# TX_fsi6.net
KiCad netlist of a schematic drawn in Altium Designer
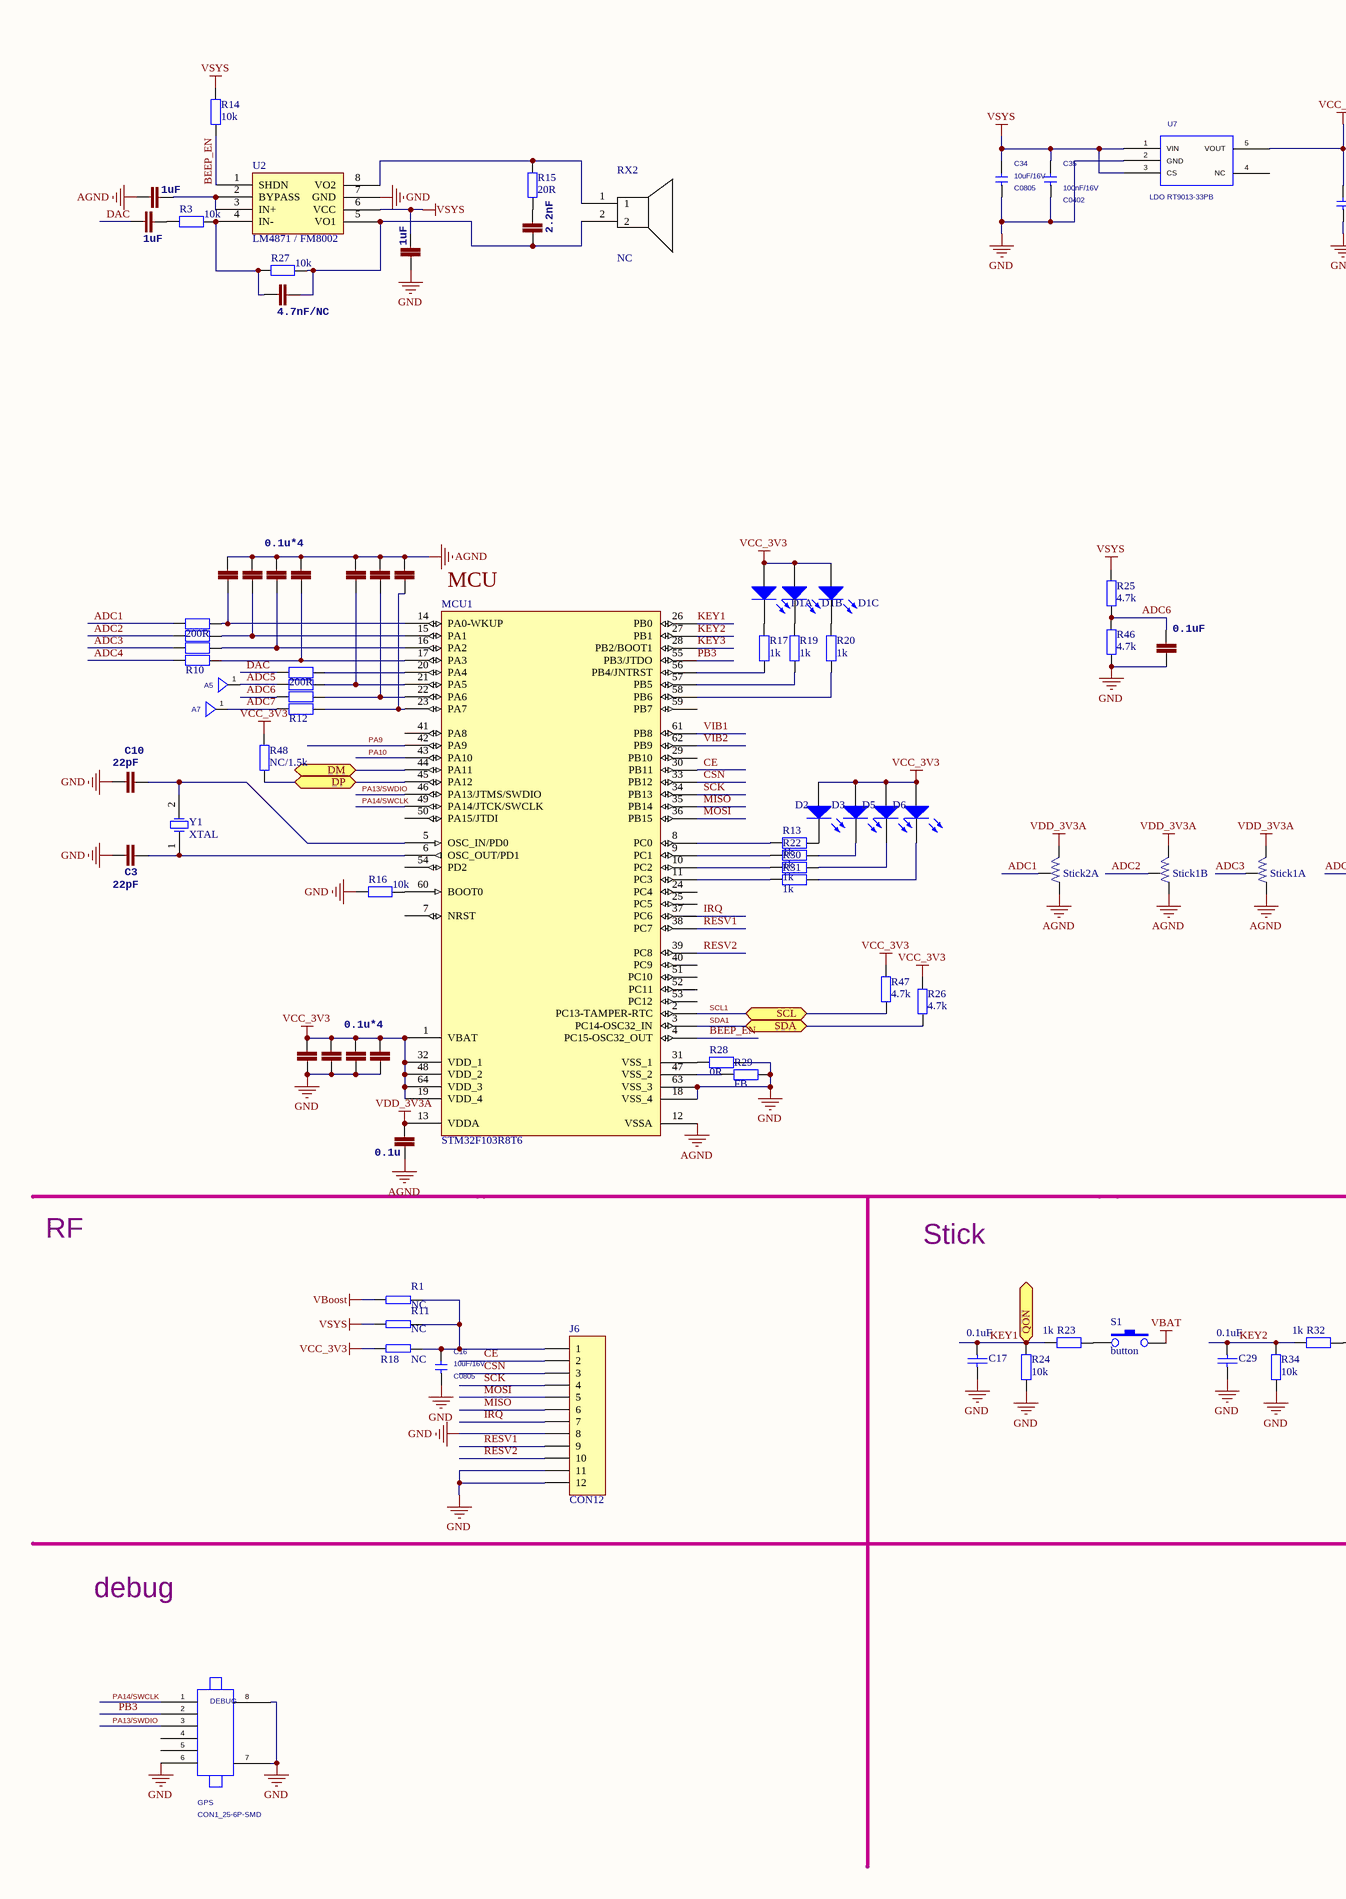
[diagram p0: TX_fsi6.SchDoc, left]
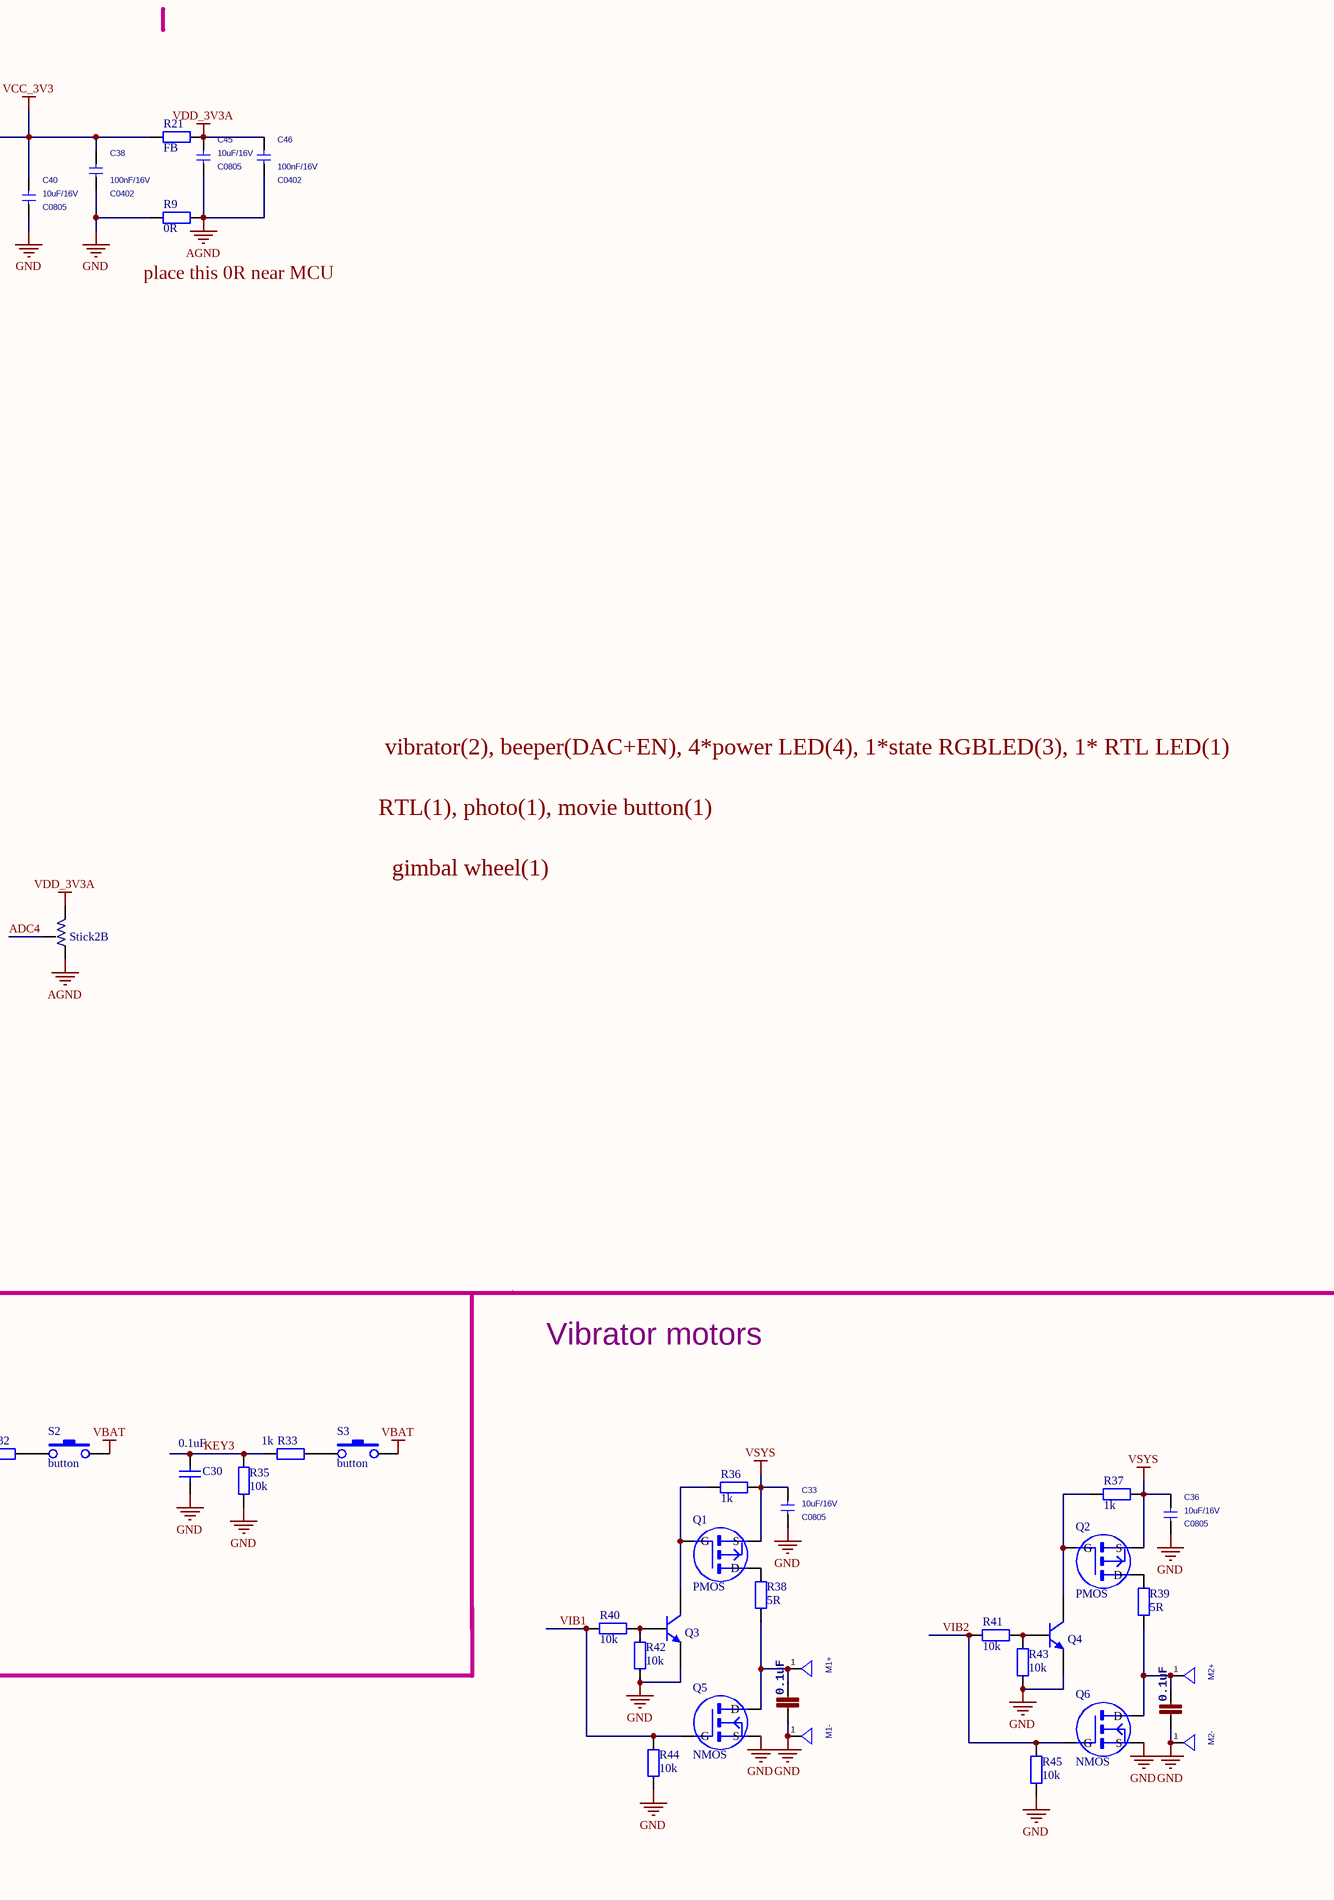
[diagram p1: TX_fsi6.SchDoc, right]

(export (version "E")
  (design (tool "Eeschema 10.0.6"))
  (components
    (comp (ref "A5") (value "~") (footprint "TestPad - 1mm") (libsource (lib "*") (part "TP_5")))
    (comp (ref "A7") (value "~") (footprint "TestPad - 1mm") (libsource (lib "*") (part "TP_5")))
    (comp (ref "C3")
      (value "22pF")
      (footprint "0402")
      (description "<b>Capacitor</b>\nStandard 0603 ceramic capacitor, and 0.1\" leaded capacitor.")
      (fields (field (name "PARTNO") "CC0402ZRY5V7BB104"))
      (libsource (lib "*") (part "CAP0402-CAP"))
    )
    (comp (ref "C7")
      (value "1n")
      (footprint "0402")
      (description "<b>Capacitor</b>\nStandard 0603 ceramic capacitor, and 0.1\" leaded capacitor.")
      (fields (field (name "PARTNO") "CC0402ZRY5V7BB104"))
      (libsource (lib "pixhawk2") (part "CAP0402-CAP"))
    )
    (comp (ref "C8")
      (value "1n")
      (footprint "0402")
      (description "<b>Capacitor</b>\nStandard 0603 ceramic capacitor, and 0.1\" leaded capacitor.")
      (fields (field (name "PARTNO") "CC0402ZRY5V7BB104"))
      (libsource (lib "pixhawk2") (part "CAP0402-CAP"))
    )
    (comp (ref "C9")
      (value "1n")
      (footprint "0402")
      (description "<b>Capacitor</b>\nStandard 0603 ceramic capacitor, and 0.1\" leaded capacitor.")
      (fields (field (name "PARTNO") "CC0402ZRY5V7BB104"))
      (libsource (lib "pixhawk2") (part "CAP0402-CAP"))
    )
    (comp (ref "C10")
      (value "22pF")
      (footprint "0402")
      (description "<b>Capacitor</b>\nStandard 0603 ceramic capacitor, and 0.1\" leaded capacitor.")
      (fields (field (name "PARTNO") "CC0402ZRY5V7BB104"))
      (libsource (lib "") (part "CAP0402-CAP_2"))
    )
    (comp (ref "C11")
      (value "0.1u*4")
      (footprint "0402")
      (description "<b>Capacitor</b>\nStandard 0603 ceramic capacitor, and 0.1\" leaded capacitor.")
      (fields (field (name "PARTNO") "CC0402ZRY5V7BB104"))
      (libsource (lib "pixhawk2") (part "CAP0402-CAP"))
    )
    (comp (ref "C12")
      (value "0.1u")
      (footprint "0402")
      (description "<b>Capacitor</b>\nStandard 0603 ceramic capacitor, and 0.1\" leaded capacitor.")
      (fields (field (name "PARTNO") "CC0402ZRY5V7BB104"))
      (libsource (lib "pixhawk2") (part "CAP0402-CAP"))
    )
    (comp (ref "C16")
      (value "10uF/16V")
      (footprint "0805")
      (fields (field (name "PCB DECAL") "C0805") (field (name "Comment") "C"))
      (libsource (lib "*") (part "C"))
    )
    (comp (ref "C17")
      (value "0.1uF")
      (footprint "0402")
      (description "Capacitor")
      (fields (field (name "PUBLISHER") "Altium Limited"))
      (libsource (lib "RTC6705") (part "Cap"))
    )
    (comp (ref "C18")
      (value "0.1u*4")
      (footprint "0402")
      (description "<b>Capacitor</b>\nStandard 0603 ceramic capacitor, and 0.1\" leaded capacitor.")
      (fields (field (name "PARTNO") "CC0402ZRY5V7BB104"))
      (libsource (lib "pixhawk2") (part "CAP0402-CAP"))
    )
    (comp (ref "C19")
      (value "1n")
      (footprint "0402")
      (description "<b>Capacitor</b>\nStandard 0603 ceramic capacitor, and 0.1\" leaded capacitor.")
      (fields (field (name "PARTNO") "CC0402ZRY5V7BB104"))
      (libsource (lib "pixhawk2") (part "CAP0402-CAP"))
    )
    (comp (ref "C20")
      (value "1n")
      (footprint "0402")
      (description "<b>Capacitor</b>\nStandard 0603 ceramic capacitor, and 0.1\" leaded capacitor.")
      (fields (field (name "PARTNO") "CC0402ZRY5V7BB104"))
      (libsource (lib "pixhawk2") (part "CAP0402-CAP"))
    )
    (comp (ref "C21")
      (value "1n")
      (footprint "0402")
      (description "<b>Capacitor</b>\nStandard 0603 ceramic capacitor, and 0.1\" leaded capacitor.")
      (fields (field (name "PARTNO") "CC0402ZRY5V7BB104"))
      (libsource (lib "pixhawk2") (part "CAP0402-CAP"))
    )
    (comp (ref "C22")
      (value "1n")
      (footprint "0402")
      (description "<b>Capacitor</b>\nStandard 0603 ceramic capacitor, and 0.1\" leaded capacitor.")
      (fields (field (name "PARTNO") "CC0402ZRY5V7BB104"))
      (libsource (lib "pixhawk2") (part "CAP0402-CAP"))
    )
    (comp (ref "C23")
      (value "1n")
      (footprint "0402")
      (description "<b>Capacitor</b>\nStandard 0603 ceramic capacitor, and 0.1\" leaded capacitor.")
      (fields (field (name "PARTNO") "CC0402ZRY5V7BB104"))
      (libsource (lib "pixhawk2") (part "CAP0402-CAP"))
    )
    (comp (ref "C24")
      (value "1n")
      (footprint "0402")
      (description "<b>Capacitor</b>\nStandard 0603 ceramic capacitor, and 0.1\" leaded capacitor.")
      (fields (field (name "PARTNO") "CC0402ZRY5V7BB104"))
      (libsource (lib "pixhawk2") (part "CAP0402-CAP"))
    )
    (comp (ref "C25")
      (value "1uF")
      (footprint "0603")
      (description "<b>Capacitor</b>\nStandard 0603 ceramic capacitor, and 0.1\" leaded capacitor.")
      (fields (field (name "PARTNO") "CC0402ZRY5V7BB104"))
      (libsource (lib "") (part "CAP0402-CAP_2"))
    )
    (comp (ref "C26")
      (value "1uF")
      (footprint "0603")
      (description "<b>Capacitor</b>\nStandard 0603 ceramic capacitor, and 0.1\" leaded capacitor.")
      (fields (field (name "PARTNO") "CC0402ZRY5V7BB104"))
      (libsource (lib "") (part "CAP0402-CAP_2"))
    )
    (comp (ref "C27")
      (value "4.7nF/NC")
      (footprint "0402")
      (description "<b>Capacitor</b>\nStandard 0603 ceramic capacitor, and 0.1\" leaded capacitor.")
      (fields (field (name "PARTNO") "CC0402ZRY5V7BB104"))
      (libsource (lib "") (part "CAP0402-CAP_2"))
    )
    (comp (ref "C28")
      (value "1uF")
      (footprint "0603")
      (description "<b>Capacitor</b>\nStandard 0603 ceramic capacitor, and 0.1\" leaded capacitor.")
      (fields (field (name "PARTNO") "CC0402ZRY5V7BB104"))
      (libsource (lib "") (part "CAP0402-CAP_1"))
    )
    (comp (ref "C29")
      (value "0.1uF")
      (footprint "0402")
      (description "Capacitor")
      (fields (field (name "PUBLISHER") "Altium Limited"))
      (libsource (lib "RTC6705") (part "Cap"))
    )
    (comp (ref "C30")
      (value "0.1uF")
      (footprint "0402")
      (description "Capacitor")
      (fields (field (name "PUBLISHER") "Altium Limited"))
      (libsource (lib "RTC6705") (part "Cap"))
    )
    (comp (ref "C32")
      (value "2.2nF")
      (footprint "0402")
      (description "<b>Capacitor</b>\nStandard 0603 ceramic capacitor, and 0.1\" leaded capacitor.")
      (fields (field (name "PARTNO") "CC0402ZRY5V7BB104"))
      (libsource (lib "") (part "CAP0402-CAP_1"))
    )
    (comp (ref "C33")
      (value "10uF/16V")
      (footprint "0805")
      (fields (field (name "PCB DECAL") "C0805") (field (name "Comment") "C"))
      (libsource (lib "*") (part "C"))
    )
    (comp (ref "C34")
      (value "10uF/16V")
      (footprint "0805")
      (fields (field (name "PCB DECAL") "C0805") (field (name "Comment") "C"))
      (libsource (lib "*") (part "C"))
    )
    (comp (ref "C35")
      (value "100nF/16V")
      (footprint "0603")
      (fields (field (name "PCB DECAL") "C0402") (field (name "Comment") "C"))
      (libsource (lib "*") (part "C"))
    )
    (comp (ref "C36")
      (value "10uF/16V")
      (footprint "0805")
      (fields (field (name "PCB DECAL") "C0805") (field (name "Comment") "C"))
      (libsource (lib "*") (part "C"))
    )
    (comp (ref "C37")
      (value "0.1uF")
      (footprint "0603")
      (description "<b>Capacitor</b>\nStandard 0603 ceramic capacitor, and 0.1\" leaded capacitor.")
      (fields (field (name "PARTNO") "CC0402ZRY5V7BB104"))
      (libsource (lib "") (part "CAP0402-CAP_1"))
    )
    (comp (ref "C38")
      (value "100nF/16V")
      (footprint "0603")
      (fields (field (name "PCB DECAL") "C0402") (field (name "Comment") "C"))
      (libsource (lib "*") (part "C"))
    )
    (comp (ref "C39")
      (value "0.1uF")
      (footprint "0603")
      (description "<b>Capacitor</b>\nStandard 0603 ceramic capacitor, and 0.1\" leaded capacitor.")
      (fields (field (name "PARTNO") "CC0402ZRY5V7BB104"))
      (libsource (lib "") (part "CAP0402-CAP_1"))
    )
    (comp (ref "C40")
      (value "10uF/16V")
      (footprint "0805")
      (fields (field (name "PCB DECAL") "C0805") (field (name "Comment") "C"))
      (libsource (lib "*") (part "C"))
    )
    (comp (ref "C41")
      (value "0.1uF")
      (footprint "0402")
      (description "<b>Capacitor</b>\nStandard 0603 ceramic capacitor, and 0.1\" leaded capacitor.")
      (fields (field (name "PARTNO") "CC0402ZRY5V7BB104"))
      (libsource (lib "pixhawk2") (part "CAP0402-CAP"))
    )
    (comp (ref "C45")
      (value "10uF/16V")
      (footprint "0805")
      (fields (field (name "PCB DECAL") "C0805") (field (name "Comment") "C"))
      (libsource (lib "*") (part "C"))
    )
    (comp (ref "C46")
      (value "100nF/16V")
      (footprint "0603")
      (fields (field (name "PCB DECAL") "C0402") (field (name "Comment") "C"))
      (libsource (lib "*") (part "C"))
    )
    (comp (ref "D1")
      (value "LEDx3")
      (footprint "LC-0603_Rx2")
      (description "Typical RED GaAs LED")
      (fields (field (name "PUBLISHER") "Altium Limited"))
      (libsource (lib "sch") (part "LEDx3"))
    )
    (comp (ref "D2")
      (value "LED0")
      (footprint "0603")
      (description "Typical INFRARED GaAs LED")
      (fields (field (name "PUBLISHER") "Altium Limited"))
      (libsource (lib "Miscellaneous Devices") (part "LED0"))
    )
    (comp (ref "D3")
      (value "LED0")
      (footprint "0603")
      (description "Typical INFRARED GaAs LED")
      (fields (field (name "PUBLISHER") "Altium Limited"))
      (libsource (lib "Miscellaneous Devices") (part "LED0"))
    )
    (comp (ref "D5")
      (value "LED0")
      (footprint "0603")
      (description "Typical INFRARED GaAs LED")
      (fields (field (name "PUBLISHER") "Altium Limited"))
      (libsource (lib "Miscellaneous Devices") (part "LED0"))
    )
    (comp (ref "D6")
      (value "LED0")
      (footprint "0603")
      (description "Typical INFRARED GaAs LED")
      (fields (field (name "PUBLISHER") "Altium Limited"))
      (libsource (lib "Miscellaneous Devices") (part "LED0"))
    )
    (comp (ref "DEBUG")
      (value "GPS")
      (footprint "CON1_25-6P-SMD")
      (fields (field (name "PCB DECAL") "CON1_25-6P-SMD") (field (name "Comment") "J12"))
      (libsource (lib "*") (part "J12"))
    )
    (comp (ref "J6")
      (value "CON12")
      (footprint "RF_AS01_SPIPX")
      (description "Connector")
      (libsource (lib "TITR-2011") (part "CON12"))
    )
    (comp (ref "M1+") (value "~") (footprint "TestPad") (libsource (lib "*") (part "TP_5")))
    (comp (ref "M1-") (value "~") (footprint "TestPad") (libsource (lib "*") (part "TP_5")))
    (comp (ref "M2+") (value "~") (footprint "TestPad") (libsource (lib "*") (part "TP_5")))
    (comp (ref "M2-") (value "~") (footprint "TestPad") (libsource (lib "*") (part "TP_5")))
    (comp (ref "MCU1")
      (value "STM32F103R8T6")
      (footprint "LQFP64_N")
      (description "STM32 ARM-based 32-bit MCU with 64 Kbytes Flash, 64-pin LQFP, Industrial Temperature")
      (fields (field (name "PUBLISHER") "*"))
      (libsource (lib "ST Microcontroller 32-Bit STM32 SCH") (part "STM32F103R8T6"))
    )
    (comp (ref "Q1") (value "PMOS") (footprint "SOT-23B_L") (libsource (lib "sch") (part "PMOS")))
    (comp (ref "Q2") (value "PMOS") (footprint "SOT-23B_L") (libsource (lib "sch") (part "PMOS")))
    (comp (ref "Q3")
      (value "NPN")
      (footprint "SOT-23B_L")
      (description "NPN Bipolar Transistor")
      (fields (field (name "PUBLISHER") "Altium Limited"))
      (libsource (lib "sch") (part "NPN"))
    )
    (comp (ref "Q4")
      (value "NPN")
      (footprint "SOT-23B_L")
      (description "NPN Bipolar Transistor")
      (fields (field (name "PUBLISHER") "Altium Limited"))
      (libsource (lib "sch") (part "NPN"))
    )
    (comp (ref "Q5") (value "NMOS") (footprint "SOT-23B_L") (libsource (lib "sch") (part "NMOS")))
    (comp (ref "Q6") (value "NMOS") (footprint "SOT-23B_L") (libsource (lib "sch") (part "NMOS")))
    (comp (ref "R1") (value "NC") (footprint "0603") (libsource (lib "Robomasters") (part "Res")))
    (comp (ref "R3")
      (value "10k")
      (footprint "0402")
      (description "Resistor")
      (fields (field (name "PUBLISHER") "Altium Limited"))
      (libsource (lib "") (part "Res2_2"))
    )
    (comp (ref "R9")
      (value "0R")
      (footprint "0402")
      (description "Resistor")
      (fields (field (name "PUBLISHER") "Altium Limited"))
      (libsource (lib "RTC6705") (part "Res2"))
    )
    (comp (ref "R10")
      (value "200R")
      (footprint "0402X4")
      (description "Resistor")
      (fields (field (name "PUBLISHER") "Altium Limited"))
      (libsource (lib "sch") (part "Res*4"))
    )
    (comp (ref "R11") (value "NC") (footprint "0603") (libsource (lib "Robomasters") (part "Res")))
    (comp (ref "R12")
      (value "200R")
      (footprint "0402X4")
      (description "Resistor")
      (fields (field (name "PUBLISHER") "Altium Limited"))
      (libsource (lib "sch") (part "Res*4"))
    )
    (comp (ref "R13")
      (value "1k")
      (footprint "0402")
      (description "Resistor")
      (fields (field (name "PUBLISHER") "Altium Limited"))
      (libsource (lib "") (part "Res2_1"))
    )
    (comp (ref "R14")
      (value "10k")
      (footprint "0402")
      (description "Resistor")
      (fields (field (name "PUBLISHER") "Altium Limited"))
      (libsource (lib "Miscellaneous Devices") (part "Res2"))
    )
    (comp (ref "R15")
      (value "20R")
      (footprint "0402")
      (description "Resistor")
      (fields (field (name "PUBLISHER") "Altium Limited"))
      (libsource (lib "Miscellaneous Devices") (part "Res2"))
    )
    (comp (ref "R16")
      (value "10k")
      (footprint "0402")
      (description "Resistor")
      (fields (field (name "PUBLISHER") "Altium Limited"))
      (libsource (lib "") (part "Res2_2"))
    )
    (comp (ref "R17")
      (value "1k")
      (footprint "0402")
      (description "Resistor")
      (fields (field (name "PUBLISHER") "Altium Limited"))
      (libsource (lib "Miscellaneous Devices") (part "Res2"))
    )
    (comp (ref "R18") (value "NC") (footprint "0603") (libsource (lib "Robomasters") (part "Res")))
    (comp (ref "R19")
      (value "1k")
      (footprint "0402")
      (description "Resistor")
      (fields (field (name "PUBLISHER") "Altium Limited"))
      (libsource (lib "Miscellaneous Devices") (part "Res2"))
    )
    (comp (ref "R20")
      (value "1k")
      (footprint "0402")
      (description "Resistor")
      (fields (field (name "PUBLISHER") "Altium Limited"))
      (libsource (lib "Miscellaneous Devices") (part "Res2"))
    )
    (comp (ref "R21")
      (value "FB")
      (footprint "0402")
      (description "Resistor")
      (fields (field (name "PUBLISHER") "Altium Limited"))
      (libsource (lib "RTC6705") (part "Res2"))
    )
    (comp (ref "R22")
      (value "1k")
      (footprint "0402")
      (description "Resistor")
      (fields (field (name "PUBLISHER") "Altium Limited"))
      (libsource (lib "") (part "Res2_1"))
    )
    (comp (ref "R23")
      (value "1k")
      (footprint "0402")
      (description "Resistor")
      (fields (field (name "PUBLISHER") "Altium Limited"))
      (libsource (lib "") (part "Res2_2"))
    )
    (comp (ref "R24")
      (value "10k")
      (footprint "0402")
      (description "Resistor")
      (fields (field (name "PUBLISHER") "Altium Limited"))
      (libsource (lib "") (part "Res2_1"))
    )
    (comp (ref "R25")
      (value "4.7k")
      (footprint "0402")
      (description "Resistor")
      (fields (field (name "PUBLISHER") "Altium Limited"))
      (libsource (lib "") (part "Res2_1"))
    )
    (comp (ref "R26")
      (value "4.7k")
      (footprint "0402")
      (description "Resistor")
      (fields (field (name "PUBLISHER") "Altium Limited"))
      (libsource (lib "") (part "Res2_1"))
    )
    (comp (ref "R27")
      (value "10k")
      (footprint "0402")
      (description "Resistor")
      (fields (field (name "PUBLISHER") "Altium Limited"))
      (libsource (lib "") (part "Res2_2"))
    )
    (comp (ref "R28")
      (value "0R")
      (footprint "0402")
      (description "Resistor")
      (fields (field (name "PUBLISHER") "Altium Limited"))
      (libsource (lib "RTC6705") (part "Res2"))
    )
    (comp (ref "R29")
      (value "FB")
      (footprint "0402")
      (description "Resistor")
      (fields (field (name "PUBLISHER") "Altium Limited"))
      (libsource (lib "RTC6705") (part "Res2"))
    )
    (comp (ref "R30")
      (value "1k")
      (footprint "0402")
      (description "Resistor")
      (fields (field (name "PUBLISHER") "Altium Limited"))
      (libsource (lib "") (part "Res2_1"))
    )
    (comp (ref "R31")
      (value "1k")
      (footprint "0402")
      (description "Resistor")
      (fields (field (name "PUBLISHER") "Altium Limited"))
      (libsource (lib "") (part "Res2_1"))
    )
    (comp (ref "R32")
      (value "1k")
      (footprint "0402")
      (description "Resistor")
      (fields (field (name "PUBLISHER") "Altium Limited"))
      (libsource (lib "") (part "Res2_2"))
    )
    (comp (ref "R33")
      (value "1k")
      (footprint "0402")
      (description "Resistor")
      (fields (field (name "PUBLISHER") "Altium Limited"))
      (libsource (lib "") (part "Res2_2"))
    )
    (comp (ref "R34")
      (value "10k")
      (footprint "0402")
      (description "Resistor")
      (fields (field (name "PUBLISHER") "Altium Limited"))
      (libsource (lib "") (part "Res2_1"))
    )
    (comp (ref "R35")
      (value "10k")
      (footprint "0402")
      (description "Resistor")
      (fields (field (name "PUBLISHER") "Altium Limited"))
      (libsource (lib "") (part "Res2_1"))
    )
    (comp (ref "R36")
      (value "1k")
      (footprint "0402")
      (description "Resistor")
      (fields (field (name "PUBLISHER") "Altium Limited"))
      (libsource (lib "RTC6705") (part "Res2"))
    )
    (comp (ref "R37")
      (value "1k")
      (footprint "0402")
      (description "Resistor")
      (fields (field (name "PUBLISHER") "Altium Limited"))
      (libsource (lib "RTC6705") (part "Res2"))
    )
    (comp (ref "R38")
      (value "5R")
      (footprint "0603")
      (description "Resistor")
      (fields (field (name "PUBLISHER") "Altium Limited"))
      (libsource (lib "") (part "Res2_1"))
    )
    (comp (ref "R39")
      (value "5R")
      (footprint "0603")
      (description "Resistor")
      (fields (field (name "PUBLISHER") "Altium Limited"))
      (libsource (lib "") (part "Res2_1"))
    )
    (comp (ref "R40")
      (value "10k")
      (footprint "0402")
      (description "Resistor")
      (fields (field (name "PUBLISHER") "Altium Limited"))
      (libsource (lib "RTC6705") (part "Res2"))
    )
    (comp (ref "R41")
      (value "10k")
      (footprint "0402")
      (description "Resistor")
      (fields (field (name "PUBLISHER") "Altium Limited"))
      (libsource (lib "RTC6705") (part "Res2"))
    )
    (comp (ref "R42")
      (value "10k")
      (footprint "0402")
      (description "Resistor")
      (fields (field (name "PUBLISHER") "Altium Limited"))
      (libsource (lib "") (part "Res2_1"))
    )
    (comp (ref "R43")
      (value "10k")
      (footprint "0402")
      (description "Resistor")
      (fields (field (name "PUBLISHER") "Altium Limited"))
      (libsource (lib "") (part "Res2_1"))
    )
    (comp (ref "R44")
      (value "10k")
      (footprint "0402")
      (description "Resistor")
      (fields (field (name "PUBLISHER") "Altium Limited"))
      (libsource (lib "") (part "Res2_1"))
    )
    (comp (ref "R45")
      (value "10k")
      (footprint "0402")
      (description "Resistor")
      (fields (field (name "PUBLISHER") "Altium Limited"))
      (libsource (lib "") (part "Res2_1"))
    )
    (comp (ref "R46")
      (value "4.7k")
      (footprint "0402")
      (description "Resistor")
      (fields (field (name "PUBLISHER") "Altium Limited"))
      (libsource (lib "") (part "Res2_1"))
    )
    (comp (ref "R47")
      (value "4.7k")
      (footprint "0402")
      (description "Resistor")
      (fields (field (name "PUBLISHER") "Altium Limited"))
      (libsource (lib "") (part "Res2_1"))
    )
    (comp (ref "R48")
      (value "NC/1.5k")
      (footprint "0402")
      (description "Resistor")
      (fields (field (name "PUBLISHER") "Altium Limited"))
      (libsource (lib "") (part "Res2_1"))
    )
    (comp (ref "RX2") (value "NC") (footprint "sonar-10mm") (libsource (lib "schlib") (part "sonar")))
    (comp (ref "S1")
      (value "button")
      (footprint "RubberButton-8mm")
      (libsource (lib "Euler") (part "button"))
    )
    (comp (ref "S2")
      (value "button")
      (footprint "RubberButton-8mm")
      (libsource (lib "Euler") (part "button"))
    )
    (comp (ref "S3")
      (value "button")
      (footprint "RubberButton-8mm")
      (libsource (lib "Euler") (part "button"))
    )
    (comp (ref "Stick1") (value "stick") (footprint "stick") (libsource (lib "sch") (part "stick")))
    (comp (ref "Stick2") (value "stick") (footprint "stick") (libsource (lib "sch") (part "stick")))
    (comp (ref "U2")
      (value "LM4871 / FM8002")
      (footprint "SOIC8_39MM")
      (libsource (lib "sch") (part "LM4871"))
    )
    (comp (ref "U7")
      (value "LDO RT9013-33PB")
      (footprint "SOT23-5")
      (fields (field (name "Comment") "RT9193-33_1_2"))
      (libsource (lib "*") (part "RT9193-33_1_2"))
    )
    (comp (ref "Y1")
      (value "XTAL")
      (footprint "OSCILLATOR-3.2X2.5 - 2P")
      (description "Crystal Oscillator")
      (fields (field (name "PUBLISHER") "Altium Limited"))
      (libsource (lib "Miscellaneous Devices") (part "XTAL"))
    )
  )
  (nets
    (net (code "1") (name "/ADC1") (class "Default")
      (node (ref "R10") (pin "1") (pinfunction "1_1") (pintype "passive"))
      (node (ref "Stick2") (pin "2") (pinfunction "2_2") (pintype "passive"))
    )
    (net (code "2") (name "/ADC2") (class "Default")
      (node (ref "R10") (pin "2") (pinfunction "2_2") (pintype "passive"))
      (node (ref "Stick1") (pin "5") (pinfunction "5_5") (pintype "passive"))
    )
    (net (code "3") (name "/ADC3") (class "Default")
      (node (ref "R10") (pin "3") (pinfunction "3_3") (pintype "passive"))
      (node (ref "Stick1") (pin "2") (pinfunction "2_2") (pintype "passive"))
    )
    (net (code "4") (name "/ADC4") (class "Default")
      (node (ref "R10") (pin "4") (pinfunction "4_4") (pintype "passive"))
      (node (ref "Stick2") (pin "5") (pinfunction "5_5") (pintype "passive"))
    )
    (net (code "5") (name "/ADC5") (class "Default")
      (node (ref "A5") (pin "1") (pinfunction "1_1") (pintype "passive"))
      (node (ref "R12") (pin "2") (pinfunction "2_2") (pintype "passive"))
    )
    (net (code "6") (name "/ADC6") (class "Default")
      (node (ref "C41") (pin "2") (pinfunction "2_2") (pintype "passive"))
      (node (ref "R12") (pin "3") (pinfunction "3_3") (pintype "passive"))
      (node (ref "R25") (pin "1") (pinfunction "1_1") (pintype "passive"))
      (node (ref "R46") (pin "2") (pinfunction "2_2") (pintype "passive"))
    )
    (net (code "7") (name "/ADC7") (class "Default")
      (node (ref "A7") (pin "1") (pinfunction "1_1") (pintype "passive"))
      (node (ref "R12") (pin "4") (pinfunction "4_4") (pintype "passive"))
    )
    (net (code "8") (name "/BEEP_EN") (class "Default")
      (node (ref "MCU1") (pin "4") (pinfunction "PC15-OSC32_OUT_4") (pintype "bidirectional"))
      (node (ref "R14") (pin "1") (pinfunction "1_1") (pintype "passive"))
      (node (ref "U2") (pin "1") (pinfunction "SHDN_1") (pintype "passive"))
    )
    (net (code "9") (name "/CE") (class "Default")
      (node (ref "J6") (pin "2") (pinfunction "2_2") (pintype "passive"))
      (node (ref "MCU1") (pin "30") (pinfunction "PB11_30") (pintype "bidirectional"))
    )
    (net (code "10") (name "/CSN") (class "Default")
      (node (ref "J6") (pin "3") (pinfunction "3_3") (pintype "passive"))
      (node (ref "MCU1") (pin "33") (pinfunction "PB12_33") (pintype "bidirectional"))
    )
    (net (code "11") (name "/DAC") (class "Default")
      (node (ref "C26") (pin "2") (pinfunction "2_2") (pintype "passive"))
      (node (ref "R12") (pin "1") (pinfunction "1_1") (pintype "passive"))
    )
    (net (code "12") (name "/DM") (class "Default")
      (node (ref "MCU1") (pin "44") (pinfunction "PA11_44") (pintype "bidirectional"))
    )
    (net (code "13") (name "/DP") (class "Default")
      (node (ref "MCU1") (pin "45") (pinfunction "PA12_45") (pintype "bidirectional"))
      (node (ref "R48") (pin "1") (pinfunction "1_1") (pintype "passive"))
    )
    (net (code "14") (name "/IRQ") (class "Default")
      (node (ref "J6") (pin "7") (pinfunction "7_7") (pintype "passive"))
      (node (ref "MCU1") (pin "37") (pinfunction "PC6_37") (pintype "bidirectional"))
    )
    (net (code "15") (name "/KEY1") (class "Default")
      (node (ref "C17") (pin "1") (pinfunction "1_1") (pintype "passive"))
      (node (ref "MCU1") (pin "26") (pinfunction "PB0_26") (pintype "bidirectional"))
      (node (ref "R23") (pin "1") (pinfunction "1_1") (pintype "passive"))
      (node (ref "R24") (pin "2") (pinfunction "2_2") (pintype "passive"))
    )
    (net (code "16") (name "/KEY2") (class "Default")
      (node (ref "C29") (pin "1") (pinfunction "1_1") (pintype "passive"))
      (node (ref "MCU1") (pin "27") (pinfunction "PB1_27") (pintype "bidirectional"))
      (node (ref "R32") (pin "1") (pinfunction "1_1") (pintype "passive"))
      (node (ref "R34") (pin "2") (pinfunction "2_2") (pintype "passive"))
    )
    (net (code "17") (name "/KEY3") (class "Default")
      (node (ref "C30") (pin "1") (pinfunction "1_1") (pintype "passive"))
      (node (ref "MCU1") (pin "28") (pinfunction "PB2/BOOT1_28") (pintype "bidirectional"))
      (node (ref "R33") (pin "1") (pinfunction "1_1") (pintype "passive"))
      (node (ref "R35") (pin "2") (pinfunction "2_2") (pintype "passive"))
    )
    (net (code "18") (name "/MISO") (class "Default")
      (node (ref "J6") (pin "6") (pinfunction "6_6") (pintype "passive"))
      (node (ref "MCU1") (pin "35") (pinfunction "PB14_35") (pintype "bidirectional"))
    )
    (net (code "19") (name "/MOSI") (class "Default")
      (node (ref "J6") (pin "5") (pinfunction "5_5") (pintype "passive"))
      (node (ref "MCU1") (pin "36") (pinfunction "PB15_36") (pintype "bidirectional"))
    )
    (net (code "20") (name "/PA9") (class "Default")
      (node (ref "MCU1") (pin "42") (pinfunction "PA9_42") (pintype "bidirectional"))
    )
    (net (code "21") (name "/PA10") (class "Default")
      (node (ref "MCU1") (pin "43") (pinfunction "PA10_43") (pintype "bidirectional"))
    )
    (net (code "22") (name "/PA13{slash}SWDIO") (class "Default")
      (node (ref "DEBUG") (pin "3") (pinfunction "3_3") (pintype "passive"))
      (node (ref "MCU1") (pin "46") (pinfunction "PA13/JTMS/SWDIO_46") (pintype "bidirectional"))
    )
    (net (code "23") (name "/PA14{slash}SWCLK") (class "Default")
      (node (ref "DEBUG") (pin "1") (pinfunction "1_1") (pintype "passive"))
      (node (ref "MCU1") (pin "49") (pinfunction "PA14/JTCK/SWCLK_49") (pintype "bidirectional"))
    )
    (net (code "24") (name "/PB3") (class "Default")
      (node (ref "DEBUG") (pin "2") (pinfunction "2_2") (pintype "passive"))
      (node (ref "MCU1") (pin "55") (pinfunction "PB3/JTDO_55") (pintype "bidirectional"))
    )
    (net (code "25") (name "/RESV1") (class "Default")
      (node (ref "J6") (pin "9") (pinfunction "9_9") (pintype "passive"))
      (node (ref "MCU1") (pin "38") (pinfunction "PC7_38") (pintype "bidirectional"))
    )
    (net (code "26") (name "/RESV2") (class "Default")
      (node (ref "J6") (pin "10") (pinfunction "10_10") (pintype "passive"))
      (node (ref "MCU1") (pin "39") (pinfunction "PC8_39") (pintype "bidirectional"))
    )
    (net (code "27") (name "/SCK") (class "Default")
      (node (ref "J6") (pin "4") (pinfunction "4_4") (pintype "passive"))
      (node (ref "MCU1") (pin "34") (pinfunction "PB13_34") (pintype "bidirectional"))
    )
    (net (code "28") (name "/SCL1") (class "Default")
      (node (ref "MCU1") (pin "2") (pinfunction "PC13-TAMPER-RTC_2") (pintype "bidirectional"))
      (node (ref "R47") (pin "1") (pinfunction "1_1") (pintype "passive"))
    )
    (net (code "29") (name "/SDA1") (class "Default")
      (node (ref "MCU1") (pin "3") (pinfunction "PC14-OSC32_IN_3") (pintype "bidirectional"))
      (node (ref "R26") (pin "1") (pinfunction "1_1") (pintype "passive"))
    )
    (net (code "30") (name "/VIB1") (class "Default")
      (node (ref "MCU1") (pin "61") (pinfunction "PB8_61") (pintype "bidirectional"))
      (node (ref "Q5") (pin "G") (pinfunction "G_G") (pintype "passive"))
      (node (ref "R40") (pin "2") (pinfunction "2_2") (pintype "passive"))
      (node (ref "R44") (pin "2") (pinfunction "2_2") (pintype "passive"))
    )
    (net (code "31") (name "/VIB2") (class "Default")
      (node (ref "MCU1") (pin "62") (pinfunction "PB9_62") (pintype "bidirectional"))
      (node (ref "Q6") (pin "G") (pinfunction "G_G") (pintype "passive"))
      (node (ref "R41") (pin "2") (pinfunction "2_2") (pintype "passive"))
      (node (ref "R45") (pin "2") (pinfunction "2_2") (pintype "passive"))
    )
    (net (code "32") (name "AGND") (class "Default")
      (node (ref "C12") (pin "1") (pinfunction "1_1") (pintype "passive"))
      (node (ref "C18") (pin "2") (pinfunction "2_2") (pintype "passive"))
      (node (ref "C19") (pin "2") (pinfunction "2_2") (pintype "passive"))
      (node (ref "C20") (pin "2") (pinfunction "2_2") (pintype "passive"))
      (node (ref "C21") (pin "2") (pinfunction "2_2") (pintype "passive"))
      (node (ref "C22") (pin "2") (pinfunction "2_2") (pintype "passive"))
      (node (ref "C23") (pin "2") (pinfunction "2_2") (pintype "passive"))
      (node (ref "C24") (pin "2") (pinfunction "2_2") (pintype "passive"))
      (node (ref "C25") (pin "2") (pinfunction "2_2") (pintype "passive"))
      (node (ref "C45") (pin "2") (pinfunction "2_2") (pintype "passive"))
      (node (ref "C46") (pin "2") (pinfunction "2_2") (pintype "passive"))
      (node (ref "MCU1") (pin "12") (pinfunction "VSSA_12") (pintype "power_in"))
      (node (ref "R9") (pin "1") (pinfunction "1_1") (pintype "passive"))
      (node (ref "Stick1") (pin "3") (pinfunction "3_3") (pintype "passive"))
      (node (ref "Stick1") (pin "6") (pinfunction "6_6") (pintype "passive"))
      (node (ref "Stick2") (pin "3") (pinfunction "3_3") (pintype "passive"))
      (node (ref "Stick2") (pin "6") (pinfunction "6_6") (pintype "passive"))
    )
    (net (code "33") (name "GND") (class "Default")
      (node (ref "C10") (pin "2") (pinfunction "2_2") (pintype "passive"))
      (node (ref "C11") (pin "1") (pinfunction "1_1") (pintype "passive"))
      (node (ref "C16") (pin "2") (pinfunction "2_2") (pintype "passive"))
      (node (ref "C17") (pin "2") (pinfunction "2_2") (pintype "passive"))
      (node (ref "C28") (pin "2") (pinfunction "2_2") (pintype "passive"))
      (node (ref "C29") (pin "2") (pinfunction "2_2") (pintype "passive"))
      (node (ref "C3") (pin "2") (pinfunction "2_2") (pintype "passive"))
      (node (ref "C30") (pin "2") (pinfunction "2_2") (pintype "passive"))
      (node (ref "C33") (pin "2") (pinfunction "2_2") (pintype "passive"))
      (node (ref "C34") (pin "2") (pinfunction "2_2") (pintype "passive"))
      (node (ref "C35") (pin "2") (pinfunction "2_2") (pintype "passive"))
      (node (ref "C36") (pin "2") (pinfunction "2_2") (pintype "passive"))
      (node (ref "C37") (pin "2") (pinfunction "2_2") (pintype "passive"))
      (node (ref "C38") (pin "2") (pinfunction "2_2") (pintype "passive"))
      (node (ref "C39") (pin "2") (pinfunction "2_2") (pintype "passive"))
      (node (ref "C40") (pin "2") (pinfunction "2_2") (pintype "passive"))
      (node (ref "C41") (pin "1") (pinfunction "1_1") (pintype "passive"))
      (node (ref "C7") (pin "1") (pinfunction "1_1") (pintype "passive"))
      (node (ref "C8") (pin "1") (pinfunction "1_1") (pintype "passive"))
      (node (ref "C9") (pin "1") (pinfunction "1_1") (pintype "passive"))
      (node (ref "DEBUG") (pin "6") (pinfunction "6_6") (pintype "passive"))
      (node (ref "DEBUG") (pin "7") (pinfunction "7_7") (pintype "passive"))
      (node (ref "DEBUG") (pin "8") (pinfunction "8_8") (pintype "passive"))
      (node (ref "J6") (pin "11") (pinfunction "11_11") (pintype "passive"))
      (node (ref "J6") (pin "12") (pinfunction "12_12") (pintype "passive"))
      (node (ref "J6") (pin "8") (pinfunction "8_8") (pintype "passive"))
      (node (ref "M1-") (pin "1") (pinfunction "1_1") (pintype "passive"))
      (node (ref "M2-") (pin "1") (pinfunction "1_1") (pintype "passive"))
      (node (ref "MCU1") (pin "18") (pinfunction "VSS_4_18") (pintype "power_in"))
      (node (ref "MCU1") (pin "63") (pinfunction "VSS_3_63") (pintype "power_in"))
      (node (ref "Q3") (pin "2") (pinfunction "E_2") (pintype "passive"))
      (node (ref "Q4") (pin "2") (pinfunction "E_2") (pintype "passive"))
      (node (ref "Q5") (pin "S") (pinfunction "S_S") (pintype "passive"))
      (node (ref "Q6") (pin "S") (pinfunction "S_S") (pintype "passive"))
      (node (ref "R16") (pin "1") (pinfunction "1_1") (pintype "passive"))
      (node (ref "R24") (pin "1") (pinfunction "1_1") (pintype "passive"))
      (node (ref "R28") (pin "1") (pinfunction "1_1") (pintype "passive"))
      (node (ref "R29") (pin "1") (pinfunction "1_1") (pintype "passive"))
      (node (ref "R34") (pin "1") (pinfunction "1_1") (pintype "passive"))
      (node (ref "R35") (pin "1") (pinfunction "1_1") (pintype "passive"))
      (node (ref "R42") (pin "1") (pinfunction "1_1") (pintype "passive"))
      (node (ref "R43") (pin "1") (pinfunction "1_1") (pintype "passive"))
      (node (ref "R44") (pin "1") (pinfunction "1_1") (pintype "passive"))
      (node (ref "R45") (pin "1") (pinfunction "1_1") (pintype "passive"))
      (node (ref "R46") (pin "1") (pinfunction "1_1") (pintype "passive"))
      (node (ref "R9") (pin "2") (pinfunction "2_2") (pintype "passive"))
      (node (ref "U2") (pin "7") (pinfunction "GND_7") (pintype "passive"))
      (node (ref "U7") (pin "2") (pinfunction "GND_2") (pintype "passive"))
    )
    (net (code "34") (name "Net-(C16-Pad1)") (class "Default")
      (node (ref "C16") (pin "1") (pinfunction "1_1") (pintype "passive"))
      (node (ref "J6") (pin "1") (pinfunction "1_1") (pintype "passive"))
      (node (ref "R1") (pin "1") (pinfunction "1_1") (pintype "passive"))
      (node (ref "R11") (pin "1") (pinfunction "1_1") (pintype "passive"))
      (node (ref "R18") (pin "1") (pinfunction "1_1") (pintype "passive"))
    )
    (net (code "35") (name "Net-(C26-Pad1)") (class "Default")
      (node (ref "C26") (pin "1") (pinfunction "1_1") (pintype "passive"))
      (node (ref "R3") (pin "1") (pinfunction "1_1") (pintype "passive"))
    )
    (net (code "36") (name "Net-(C32-Pad1)") (class "Default")
      (node (ref "C32") (pin "1") (pinfunction "1_1") (pintype "passive"))
      (node (ref "R15") (pin "1") (pinfunction "1_1") (pintype "passive"))
    )
    (net (code "37") (name "Net-(C37-Pad1)") (class "Default")
      (node (ref "C37") (pin "1") (pinfunction "1_1") (pintype "passive"))
      (node (ref "M1+") (pin "1") (pinfunction "1_1") (pintype "passive"))
      (node (ref "Q5") (pin "D") (pinfunction "D_D") (pintype "passive"))
      (node (ref "R38") (pin "1") (pinfunction "1_1") (pintype "passive"))
    )
    (net (code "38") (name "Net-(C39-Pad1)") (class "Default")
      (node (ref "C39") (pin "1") (pinfunction "1_1") (pintype "passive"))
      (node (ref "M2+") (pin "1") (pinfunction "1_1") (pintype "passive"))
      (node (ref "Q6") (pin "D") (pinfunction "D_D") (pintype "passive"))
      (node (ref "R39") (pin "1") (pinfunction "1_1") (pintype "passive"))
    )
    (net (code "39") (name "Net-(D1A-K)") (class "Default")
      (node (ref "D1") (pin "2") (pinfunction "K_2") (pintype "passive"))
      (node (ref "R17") (pin "2") (pinfunction "2_2") (pintype "passive"))
    )
    (net (code "40") (name "Net-(D1B-K)") (class "Default")
      (node (ref "D1") (pin "3") (pinfunction "K_3") (pintype "passive"))
      (node (ref "R19") (pin "2") (pinfunction "2_2") (pintype "passive"))
    )
    (net (code "41") (name "Net-(D1C-K)") (class "Default")
      (node (ref "D1") (pin "4") (pinfunction "K_4") (pintype "passive"))
      (node (ref "R20") (pin "2") (pinfunction "2_2") (pintype "passive"))
    )
    (net (code "42") (name "Net-(D2-K)") (class "Default")
      (node (ref "D2") (pin "2") (pinfunction "K_2") (pintype "passive"))
      (node (ref "R13") (pin "1") (pinfunction "1_1") (pintype "passive"))
    )
    (net (code "43") (name "Net-(D3-K)") (class "Default")
      (node (ref "D3") (pin "2") (pinfunction "K_2") (pintype "passive"))
      (node (ref "R22") (pin "1") (pinfunction "1_1") (pintype "passive"))
    )
    (net (code "44") (name "Net-(D5-K)") (class "Default")
      (node (ref "D5") (pin "2") (pinfunction "K_2") (pintype "passive"))
      (node (ref "R30") (pin "1") (pinfunction "1_1") (pintype "passive"))
    )
    (net (code "45") (name "Net-(D6-K)") (class "Default")
      (node (ref "D6") (pin "2") (pinfunction "K_2") (pintype "passive"))
      (node (ref "R31") (pin "1") (pinfunction "1_1") (pintype "passive"))
    )
    (net (code "46") (name "Net-(MCU1-BOOT0)") (class "Default")
      (node (ref "MCU1") (pin "60") (pinfunction "BOOT0_60") (pintype "input"))
      (node (ref "R16") (pin "2") (pinfunction "2_2") (pintype "passive"))
    )
    (net (code "47") (name "Net-(MCU1-OSC_IN{slash}PD0)") (class "Default")
      (node (ref "C10") (pin "1") (pinfunction "1_1") (pintype "passive"))
      (node (ref "MCU1") (pin "5") (pinfunction "OSC_IN/PD0_5") (pintype "input"))
      (node (ref "Y1") (pin "2") (pinfunction "OSC2_2") (pintype "passive"))
    )
    (net (code "48") (name "Net-(MCU1-OSC_OUT{slash}PD1)") (class "Default")
      (node (ref "C3") (pin "1") (pinfunction "1_1") (pintype "passive"))
      (node (ref "MCU1") (pin "6") (pinfunction "OSC_OUT/PD1_6") (pintype "output"))
      (node (ref "Y1") (pin "1") (pinfunction "OSC1_1") (pintype "passive"))
    )
    (net (code "49") (name "Net-(MCU1-PA0-WKUP)") (class "Default")
      (node (ref "C18") (pin "1") (pinfunction "1_1") (pintype "passive"))
      (node (ref "MCU1") (pin "14") (pinfunction "PA0-WKUP_14") (pintype "bidirectional"))
      (node (ref "R10") (pin "8") (pinfunction "8_8") (pintype "passive"))
    )
    (net (code "50") (name "Net-(MCU1-PA1)") (class "Default")
      (node (ref "C19") (pin "1") (pinfunction "1_1") (pintype "passive"))
      (node (ref "MCU1") (pin "15") (pinfunction "PA1_15") (pintype "bidirectional"))
      (node (ref "R10") (pin "7") (pinfunction "7_7") (pintype "passive"))
    )
    (net (code "51") (name "Net-(MCU1-PA2)") (class "Default")
      (node (ref "C20") (pin "1") (pinfunction "1_1") (pintype "passive"))
      (node (ref "MCU1") (pin "16") (pinfunction "PA2_16") (pintype "bidirectional"))
      (node (ref "R10") (pin "6") (pinfunction "6_6") (pintype "passive"))
    )
    (net (code "52") (name "Net-(MCU1-PA3)") (class "Default")
      (node (ref "C21") (pin "1") (pinfunction "1_1") (pintype "passive"))
      (node (ref "MCU1") (pin "17") (pinfunction "PA3_17") (pintype "bidirectional"))
      (node (ref "R10") (pin "5") (pinfunction "5_5") (pintype "passive"))
    )
    (net (code "53") (name "Net-(MCU1-PA4)") (class "Default")
      (node (ref "MCU1") (pin "20") (pinfunction "PA4_20") (pintype "bidirectional"))
      (node (ref "R12") (pin "8") (pinfunction "8_8") (pintype "passive"))
    )
    (net (code "54") (name "Net-(MCU1-PA5)") (class "Default")
      (node (ref "C22") (pin "1") (pinfunction "1_1") (pintype "passive"))
      (node (ref "MCU1") (pin "21") (pinfunction "PA5_21") (pintype "bidirectional"))
      (node (ref "R12") (pin "7") (pinfunction "7_7") (pintype "passive"))
    )
    (net (code "55") (name "Net-(MCU1-PA6)") (class "Default")
      (node (ref "C23") (pin "1") (pinfunction "1_1") (pintype "passive"))
      (node (ref "MCU1") (pin "22") (pinfunction "PA6_22") (pintype "bidirectional"))
      (node (ref "R12") (pin "6") (pinfunction "6_6") (pintype "passive"))
    )
    (net (code "56") (name "Net-(MCU1-PA7)") (class "Default")
      (node (ref "C24") (pin "1") (pinfunction "1_1") (pintype "passive"))
      (node (ref "MCU1") (pin "23") (pinfunction "PA7_23") (pintype "bidirectional"))
      (node (ref "R12") (pin "5") (pinfunction "5_5") (pintype "passive"))
    )
    (net (code "57") (name "Net-(MCU1-PB4{slash}JNTRST)") (class "Default")
      (node (ref "MCU1") (pin "56") (pinfunction "PB4/JNTRST_56") (pintype "bidirectional"))
      (node (ref "R17") (pin "1") (pinfunction "1_1") (pintype "passive"))
    )
    (net (code "58") (name "Net-(MCU1-PB5)") (class "Default")
      (node (ref "MCU1") (pin "57") (pinfunction "PB5_57") (pintype "bidirectional"))
      (node (ref "R19") (pin "1") (pinfunction "1_1") (pintype "passive"))
    )
    (net (code "59") (name "Net-(MCU1-PB6)") (class "Default")
      (node (ref "MCU1") (pin "58") (pinfunction "PB6_58") (pintype "bidirectional"))
      (node (ref "R20") (pin "1") (pinfunction "1_1") (pintype "passive"))
    )
    (net (code "60") (name "Net-(MCU1-PC0)") (class "Default")
      (node (ref "MCU1") (pin "8") (pinfunction "PC0_8") (pintype "bidirectional"))
      (node (ref "R13") (pin "2") (pinfunction "2_2") (pintype "passive"))
    )
    (net (code "61") (name "Net-(MCU1-PC1)") (class "Default")
      (node (ref "MCU1") (pin "9") (pinfunction "PC1_9") (pintype "bidirectional"))
      (node (ref "R22") (pin "2") (pinfunction "2_2") (pintype "passive"))
    )
    (net (code "62") (name "Net-(MCU1-PC2)") (class "Default")
      (node (ref "MCU1") (pin "10") (pinfunction "PC2_10") (pintype "bidirectional"))
      (node (ref "R30") (pin "2") (pinfunction "2_2") (pintype "passive"))
    )
    (net (code "63") (name "Net-(MCU1-PC3)") (class "Default")
      (node (ref "MCU1") (pin "11") (pinfunction "PC3_11") (pintype "bidirectional"))
      (node (ref "R31") (pin "2") (pinfunction "2_2") (pintype "passive"))
    )
    (net (code "64") (name "Net-(MCU1-VSS_1)") (class "Default")
      (node (ref "MCU1") (pin "31") (pinfunction "VSS_1_31") (pintype "power_in"))
      (node (ref "R28") (pin "2") (pinfunction "2_2") (pintype "passive"))
    )
    (net (code "65") (name "Net-(MCU1-VSS_2)") (class "Default")
      (node (ref "MCU1") (pin "47") (pinfunction "VSS_2_47") (pintype "power_in"))
      (node (ref "R29") (pin "2") (pinfunction "2_2") (pintype "passive"))
    )
    (net (code "66") (name "Net-(Q1-PadD)") (class "Default")
      (node (ref "Q1") (pin "D") (pinfunction "D_D") (pintype "passive"))
      (node (ref "R38") (pin "2") (pinfunction "2_2") (pintype "passive"))
    )
    (net (code "67") (name "Net-(Q2-PadD)") (class "Default")
      (node (ref "Q2") (pin "D") (pinfunction "D_D") (pintype "passive"))
      (node (ref "R39") (pin "2") (pinfunction "2_2") (pintype "passive"))
    )
    (net (code "68") (name "Net-(Q3-B)") (class "Default")
      (node (ref "Q3") (pin "1") (pinfunction "B_1") (pintype "passive"))
      (node (ref "R40") (pin "1") (pinfunction "1_1") (pintype "passive"))
      (node (ref "R42") (pin "2") (pinfunction "2_2") (pintype "passive"))
    )
    (net (code "69") (name "Net-(Q3-C)") (class "Default")
      (node (ref "Q1") (pin "G") (pinfunction "G_G") (pintype "passive"))
      (node (ref "Q3") (pin "3") (pinfunction "C_3") (pintype "passive"))
      (node (ref "R36") (pin "2") (pinfunction "2_2") (pintype "passive"))
    )
    (net (code "70") (name "Net-(Q4-B)") (class "Default")
      (node (ref "Q4") (pin "1") (pinfunction "B_1") (pintype "passive"))
      (node (ref "R41") (pin "1") (pinfunction "1_1") (pintype "passive"))
      (node (ref "R43") (pin "2") (pinfunction "2_2") (pintype "passive"))
    )
    (net (code "71") (name "Net-(Q4-C)") (class "Default")
      (node (ref "Q2") (pin "G") (pinfunction "G_G") (pintype "passive"))
      (node (ref "Q4") (pin "3") (pinfunction "C_3") (pintype "passive"))
      (node (ref "R37") (pin "2") (pinfunction "2_2") (pintype "passive"))
    )
    (net (code "72") (name "Net-(R23-Pad2)") (class "Default")
      (node (ref "R23") (pin "2") (pinfunction "2_2") (pintype "passive"))
      (node (ref "S1") (pin "1") (pinfunction "1_1") (pintype "passive"))
    )
    (net (code "73") (name "Net-(R32-Pad2)") (class "Default")
      (node (ref "R32") (pin "2") (pinfunction "2_2") (pintype "passive"))
      (node (ref "S2") (pin "1") (pinfunction "1_1") (pintype "passive"))
    )
    (net (code "74") (name "Net-(R33-Pad2)") (class "Default")
      (node (ref "R33") (pin "2") (pinfunction "2_2") (pintype "passive"))
      (node (ref "S3") (pin "1") (pinfunction "1_1") (pintype "passive"))
    )
    (net (code "75") (name "Net-(U2-BYPASS)") (class "Default")
      (node (ref "C25") (pin "1") (pinfunction "1_1") (pintype "passive"))
      (node (ref "U2") (pin "2") (pinfunction "BYPASS_2") (pintype "passive"))
      (node (ref "U2") (pin "3") (pinfunction "IN+_3") (pintype "passive"))
    )
    (net (code "76") (name "Net-(U2-IN-)") (class "Default")
      (node (ref "C27") (pin "2") (pinfunction "2_2") (pintype "passive"))
      (node (ref "R27") (pin "1") (pinfunction "1_1") (pintype "passive"))
      (node (ref "R3") (pin "2") (pinfunction "2_2") (pintype "passive"))
      (node (ref "U2") (pin "4") (pinfunction "IN-_4") (pintype "passive"))
    )
    (net (code "77") (name "Net-(U2-VO1)") (class "Default")
      (node (ref "C27") (pin "1") (pinfunction "1_1") (pintype "passive"))
      (node (ref "C32") (pin "2") (pinfunction "2_2") (pintype "passive"))
      (node (ref "R27") (pin "2") (pinfunction "2_2") (pintype "passive"))
      (node (ref "RX2") (pin "2") (pinfunction "2_2") (pintype "passive"))
      (node (ref "U2") (pin "5") (pinfunction "VO1_5") (pintype "passive"))
    )
    (net (code "78") (name "Net-(U2-VO2)") (class "Default")
      (node (ref "R15") (pin "2") (pinfunction "2_2") (pintype "passive"))
      (node (ref "RX2") (pin "1") (pinfunction "1_1") (pintype "passive"))
      (node (ref "U2") (pin "8") (pinfunction "VO2_8") (pintype "passive"))
    )
    (net (code "79") (name "VBAT") (class "Default")
      (node (ref "S1") (pin "2") (pinfunction "2_2") (pintype "passive"))
      (node (ref "S2") (pin "2") (pinfunction "2_2") (pintype "passive"))
      (node (ref "S3") (pin "2") (pinfunction "2_2") (pintype "passive"))
    )
    (net (code "80") (name "VBoost") (class "Default")
      (node (ref "R1") (pin "2") (pinfunction "2_2") (pintype "passive"))
    )
    (net (code "81") (name "VCC_3V3") (class "Default")
      (node (ref "C11") (pin "2") (pinfunction "2_2") (pintype "passive"))
      (node (ref "C38") (pin "1") (pinfunction "1_1") (pintype "passive"))
      (node (ref "C40") (pin "1") (pinfunction "1_1") (pintype "passive"))
      (node (ref "C7") (pin "2") (pinfunction "2_2") (pintype "passive"))
      (node (ref "C8") (pin "2") (pinfunction "2_2") (pintype "passive"))
      (node (ref "C9") (pin "2") (pinfunction "2_2") (pintype "passive"))
      (node (ref "D1") (pin "1") (pinfunction "A_1") (pintype "passive"))
      (node (ref "D2") (pin "1") (pinfunction "A_1") (pintype "passive"))
      (node (ref "D3") (pin "1") (pinfunction "A_1") (pintype "passive"))
      (node (ref "D5") (pin "1") (pinfunction "A_1") (pintype "passive"))
      (node (ref "D6") (pin "1") (pinfunction "A_1") (pintype "passive"))
      (node (ref "MCU1") (pin "1") (pinfunction "VBAT_1") (pintype "power_in"))
      (node (ref "MCU1") (pin "19") (pinfunction "VDD_4_19") (pintype "power_in"))
      (node (ref "MCU1") (pin "32") (pinfunction "VDD_1_32") (pintype "power_in"))
      (node (ref "MCU1") (pin "48") (pinfunction "VDD_2_48") (pintype "power_in"))
      (node (ref "MCU1") (pin "64") (pinfunction "VDD_3_64") (pintype "power_in"))
      (node (ref "R18") (pin "2") (pinfunction "2_2") (pintype "passive"))
      (node (ref "R21") (pin "2") (pinfunction "2_2") (pintype "passive"))
      (node (ref "R26") (pin "2") (pinfunction "2_2") (pintype "passive"))
      (node (ref "R47") (pin "2") (pinfunction "2_2") (pintype "passive"))
      (node (ref "R48") (pin "2") (pinfunction "2_2") (pintype "passive"))
      (node (ref "U7") (pin "5") (pinfunction "VOUT_5") (pintype "passive"))
    )
    (net (code "82") (name "VDD_3V3A") (class "Default")
      (node (ref "C12") (pin "2") (pinfunction "2_2") (pintype "passive"))
      (node (ref "C45") (pin "1") (pinfunction "1_1") (pintype "passive"))
      (node (ref "C46") (pin "1") (pinfunction "1_1") (pintype "passive"))
      (node (ref "MCU1") (pin "13") (pinfunction "VDDA_13") (pintype "power_in"))
      (node (ref "R21") (pin "1") (pinfunction "1_1") (pintype "passive"))
      (node (ref "Stick1") (pin "1") (pinfunction "1_1") (pintype "passive"))
      (node (ref "Stick1") (pin "4") (pinfunction "4_4") (pintype "passive"))
      (node (ref "Stick2") (pin "1") (pinfunction "1_1") (pintype "passive"))
      (node (ref "Stick2") (pin "4") (pinfunction "4_4") (pintype "passive"))
    )
    (net (code "83") (name "VSYS") (class "Default")
      (node (ref "C28") (pin "1") (pinfunction "1_1") (pintype "passive"))
      (node (ref "C33") (pin "1") (pinfunction "1_1") (pintype "passive"))
      (node (ref "C34") (pin "1") (pinfunction "1_1") (pintype "passive"))
      (node (ref "C35") (pin "1") (pinfunction "1_1") (pintype "passive"))
      (node (ref "C36") (pin "1") (pinfunction "1_1") (pintype "passive"))
      (node (ref "Q1") (pin "S") (pinfunction "S_S") (pintype "passive"))
      (node (ref "Q2") (pin "S") (pinfunction "S_S") (pintype "passive"))
      (node (ref "R11") (pin "2") (pinfunction "2_2") (pintype "passive"))
      (node (ref "R14") (pin "2") (pinfunction "2_2") (pintype "passive"))
      (node (ref "R25") (pin "2") (pinfunction "2_2") (pintype "passive"))
      (node (ref "R36") (pin "1") (pinfunction "1_1") (pintype "passive"))
      (node (ref "R37") (pin "1") (pinfunction "1_1") (pintype "passive"))
      (node (ref "U2") (pin "6") (pinfunction "VCC_6") (pintype "passive"))
      (node (ref "U7") (pin "1") (pinfunction "VIN_1") (pintype "passive"))
      (node (ref "U7") (pin "3") (pinfunction "CS_3") (pintype "passive"))
    )
    (net (code "84") (name "unconnected-(DEBUG-Pad4)") (class "Default")
      (node (ref "DEBUG") (pin "4") (pinfunction "4_4") (pintype "passive"))
    )
    (net (code "85") (name "unconnected-(DEBUG-Pad5)") (class "Default")
      (node (ref "DEBUG") (pin "5") (pinfunction "5_5") (pintype "passive"))
    )
    (net (code "86") (name "unconnected-(MCU1-NRST-Pad7)") (class "Default")
      (node (ref "MCU1") (pin "7") (pinfunction "NRST_7") (pintype "bidirectional"))
    )
    (net (code "87") (name "unconnected-(MCU1-PA8-Pad41)") (class "Default")
      (node (ref "MCU1") (pin "41") (pinfunction "PA8_41") (pintype "bidirectional"))
    )
    (net (code "88") (name "unconnected-(MCU1-PA15{slash}JTDI-Pad50)") (class "Default")
      (node (ref "MCU1") (pin "50") (pinfunction "PA15/JTDI_50") (pintype "bidirectional"))
    )
    (net (code "89") (name "unconnected-(MCU1-PB7-Pad59)") (class "Default")
      (node (ref "MCU1") (pin "59") (pinfunction "PB7_59") (pintype "bidirectional"))
    )
    (net (code "90") (name "unconnected-(MCU1-PB10-Pad29)") (class "Default")
      (node (ref "MCU1") (pin "29") (pinfunction "PB10_29") (pintype "bidirectional"))
    )
    (net (code "91") (name "unconnected-(MCU1-PC4-Pad24)") (class "Default")
      (node (ref "MCU1") (pin "24") (pinfunction "PC4_24") (pintype "bidirectional"))
    )
    (net (code "92") (name "unconnected-(MCU1-PC5-Pad25)") (class "Default")
      (node (ref "MCU1") (pin "25") (pinfunction "PC5_25") (pintype "bidirectional"))
    )
    (net (code "93") (name "unconnected-(MCU1-PC9-Pad40)") (class "Default")
      (node (ref "MCU1") (pin "40") (pinfunction "PC9_40") (pintype "bidirectional"))
    )
    (net (code "94") (name "unconnected-(MCU1-PC10-Pad51)") (class "Default")
      (node (ref "MCU1") (pin "51") (pinfunction "PC10_51") (pintype "bidirectional"))
    )
    (net (code "95") (name "unconnected-(MCU1-PC11-Pad52)") (class "Default")
      (node (ref "MCU1") (pin "52") (pinfunction "PC11_52") (pintype "bidirectional"))
    )
    (net (code "96") (name "unconnected-(MCU1-PC12-Pad53)") (class "Default")
      (node (ref "MCU1") (pin "53") (pinfunction "PC12_53") (pintype "bidirectional"))
    )
    (net (code "97") (name "unconnected-(MCU1-PD2-Pad54)") (class "Default")
      (node (ref "MCU1") (pin "54") (pinfunction "PD2_54") (pintype "bidirectional"))
    )
    (net (code "98") (name "unconnected-(U7-NC-Pad4)") (class "Default")
      (node (ref "U7") (pin "4") (pinfunction "NC_4") (pintype "passive"))
    )
  )
)
